# Temperature_Interface.net
KiCad netlist of a schematic drawn in Altium Designer
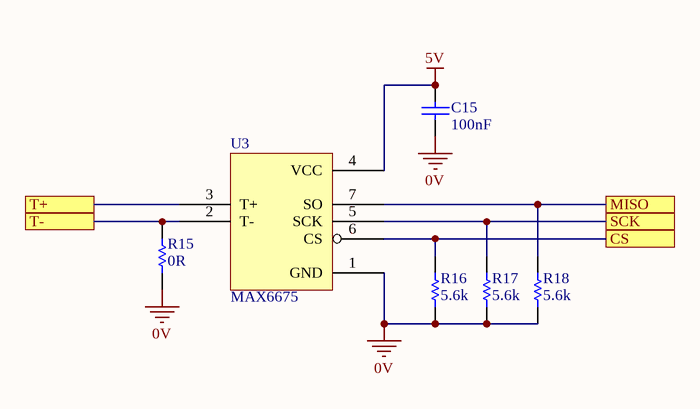
[diagram p0: Temperature Interface.SchDoc]

(export (version "E")
  (design (tool "Eeschema 10.0.6"))
  (components
    (comp (ref "C15")
      (value "100nF")
      (footprint "0805")
      (fields
        (field (name "PART NUMBER") "GCM21BR71H104KA37L")
        (field (name "TOLERANCE") "±10%")
        (field (name "MANUFACTURER") "muRata")
      )
      (libsource (lib "ts_20-standard-library") (part "Capacitor"))
    )
    (comp (ref "R15")
      (value "0R")
      (footprint "0805")
      (fields
        (field (name "PART NUMBER") "RC0805FR070RL")
        (field (name "MANUFACTURER") "YAGEO")
        (field (name "TOLERANCE") "0.01")
      )
      (libsource (lib "ts_20-standard-library") (part "Resistor"))
    )
    (comp (ref "R16")
      (value "5.6k")
      (footprint "0805")
      (fields
        (field (name "PART NUMBER") "RC0805FR075K6L")
        (field (name "MANUFACTURER") "YAGEO")
        (field (name "TOLERANCE") "0.01")
      )
      (libsource (lib "ts_20-standard-library") (part "Resistor"))
    )
    (comp (ref "R17")
      (value "5.6k")
      (footprint "0805")
      (fields
        (field (name "PART NUMBER") "RC0805FR075K6L")
        (field (name "MANUFACTURER") "YAGEO")
        (field (name "TOLERANCE") "0.01")
      )
      (libsource (lib "ts_20-standard-library") (part "Resistor"))
    )
    (comp (ref "R18")
      (value "5.6k")
      (footprint "0805")
      (fields
        (field (name "PART NUMBER") "RC0805FR075K6L")
        (field (name "MANUFACTURER") "YAGEO")
        (field (name "TOLERANCE") "0.01")
      )
      (libsource (lib "ts_20-standard-library") (part "Resistor"))
    )
    (comp (ref "U3")
      (value "MAX6675")
      (footprint "MI 8-SOIC")
      (description "IC THERMOCOUP TO DGTL 8-SOIC")
      (fields
        (field (name "MANUFACTURER") "Maxim Integrated")
        (field (name "DIGIKEY PART NUMBER") "MAX6675ISA+-ND")
      )
      (libsource (lib "ts_20-standard-library") (part "MAX6675"))
    )
  )
  (nets
    (net (code "1") (name "/CS") (class "Default")
      (node (ref "R16") (pin "2") (pinfunction "2_2") (pintype "passive"))
      (node (ref "U3") (pin "6") (pinfunction "CS_6") (pintype "power_in"))
    )
    (net (code "2") (name "/MISO") (class "Default")
      (node (ref "R18") (pin "2") (pinfunction "2_2") (pintype "passive"))
      (node (ref "U3") (pin "7") (pinfunction "SO_7") (pintype "power_in"))
    )
    (net (code "3") (name "/SCK") (class "Default")
      (node (ref "R17") (pin "2") (pinfunction "2_2") (pintype "passive"))
      (node (ref "U3") (pin "5") (pinfunction "SCK_5") (pintype "power_in"))
    )
    (net (code "4") (name "/T+") (class "Default")
      (node (ref "U3") (pin "3") (pinfunction "T+_3") (pintype "power_in"))
    )
    (net (code "5") (name "/T-") (class "Default")
      (node (ref "R15") (pin "2") (pinfunction "2_2") (pintype "passive"))
      (node (ref "U3") (pin "2") (pinfunction "T-_2") (pintype "power_in"))
    )
    (net (code "6") (name "0V") (class "Default")
      (node (ref "C15") (pin "1") (pinfunction "1_1") (pintype "passive"))
      (node (ref "R15") (pin "1") (pinfunction "1_1") (pintype "passive"))
      (node (ref "R16") (pin "1") (pinfunction "1_1") (pintype "passive"))
      (node (ref "R17") (pin "1") (pinfunction "1_1") (pintype "passive"))
      (node (ref "R18") (pin "1") (pinfunction "1_1") (pintype "passive"))
      (node (ref "U3") (pin "1") (pinfunction "GND_1") (pintype "power_in"))
    )
    (net (code "7") (name "5V") (class "Default")
      (node (ref "C15") (pin "2") (pinfunction "2_2") (pintype "passive"))
      (node (ref "U3") (pin "4") (pinfunction "VCC_4") (pintype "power_in"))
    )
  )
)
